# Adafruit_2_8_inch_TFT_w_Capacitive_Touch.net
KiCad netlist of a schematic drawn in EAGLE
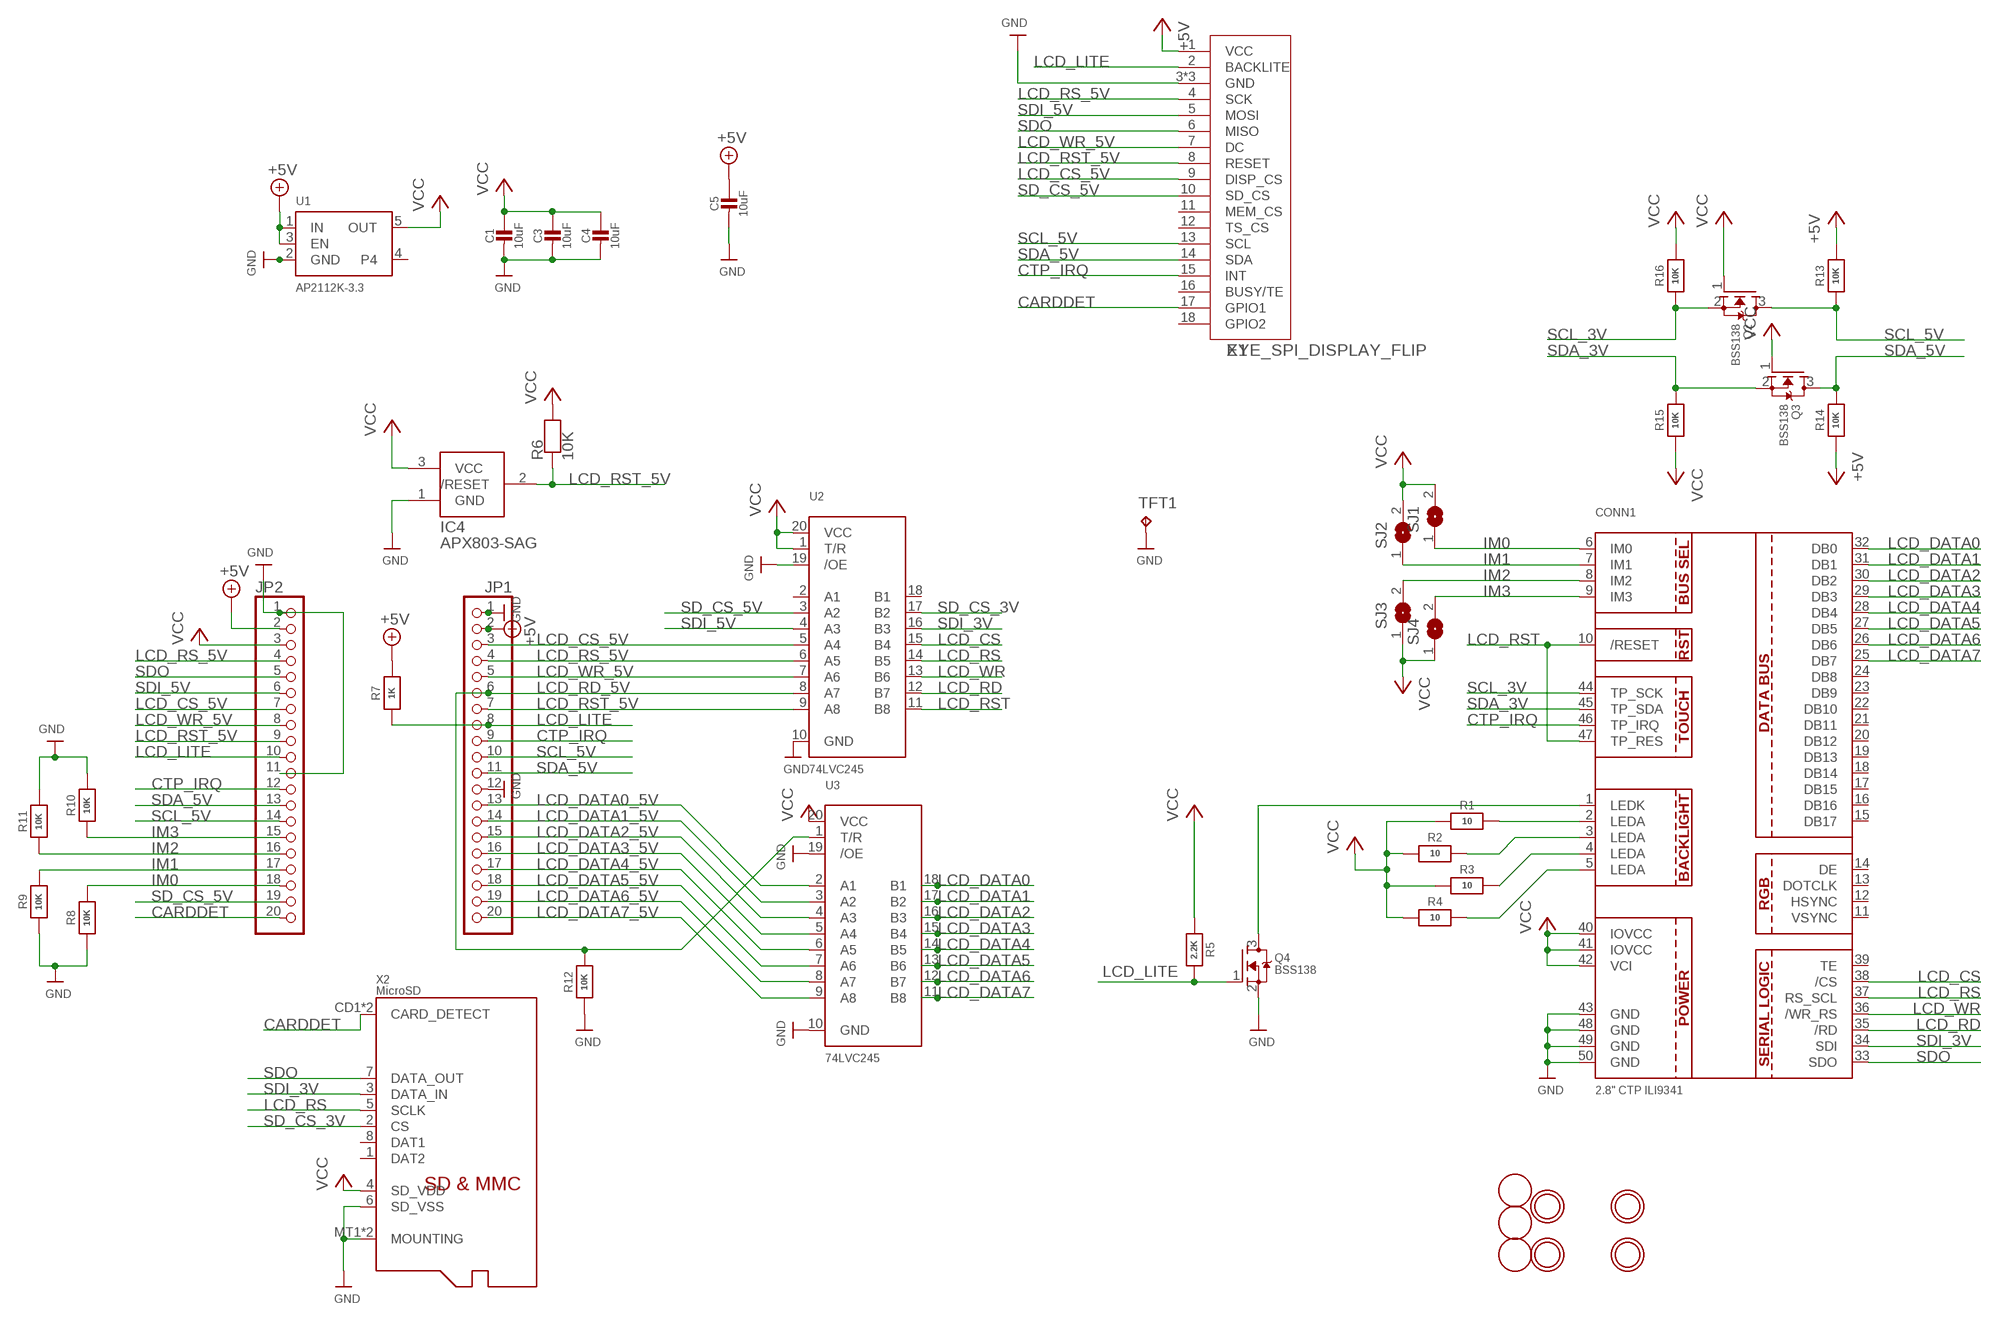
[diagram p0: schematic, sheet 1]

(export (version "E")
  (design (tool "Eeschema 10.0.6"))
  (components
    (comp (ref "C1")
      (value "10uF")
      (footprint "eagle-import:0805-NO")
      (libsource (lib "eagle-import") (part "CAP_CERAMIC0805-NOOUTLINE"))
    )
    (comp (ref "C3")
      (value "10uF")
      (footprint "eagle-import:0805-NO")
      (libsource (lib "eagle-import") (part "CAP_CERAMIC0805-NOOUTLINE"))
    )
    (comp (ref "C4")
      (value "10uF")
      (footprint "eagle-import:0805-NO")
      (libsource (lib "eagle-import") (part "CAP_CERAMIC0805-NOOUTLINE"))
    )
    (comp (ref "C5")
      (value "10uF")
      (footprint "eagle-import:0805-NO")
      (libsource (lib "eagle-import") (part "CAP_CERAMIC0805-NOOUTLINE"))
    )
    (comp (ref "CONN1")
      (value "2.8\" CTP ILI9341")
      (footprint "eagle-import:TFT_2.83IN_240X320_50PIN")
      (libsource (lib "eagle-import") (part "DISP_LCD_CTP28_SAMPLE"))
    )
    (comp (ref "IC4")
      (value "APX803-SAG")
      (footprint "eagle-import:SOT23-WIDE")
      (libsource (lib "eagle-import") (part "APX083-SAG"))
    )
    (comp (ref "JP1")
      (value "HEADER-1X20ROUND")
      (footprint "eagle-import:1X20_ROUND")
      (libsource (lib "eagle-import") (part "HEADER-1X20ROUND"))
    )
    (comp (ref "JP2")
      (value "HEADER-1X20ROUND")
      (footprint "eagle-import:1X20_ROUND")
      (libsource (lib "eagle-import") (part "HEADER-1X20ROUND"))
    )
    (comp (ref "Q2")
      (value "BSS138")
      (footprint "eagle-import:SOT23-WIDE")
      (libsource (lib "eagle-import") (part "MOSFET-NWIDE"))
    )
    (comp (ref "Q3")
      (value "BSS138")
      (footprint "eagle-import:SOT23-WIDE")
      (libsource (lib "eagle-import") (part "MOSFET-NWIDE"))
    )
    (comp (ref "Q4")
      (value "BSS138")
      (footprint "eagle-import:SOT23-WIDE")
      (libsource (lib "eagle-import") (part "MOSFET-NWIDE"))
    )
    (comp (ref "R1")
      (value "10")
      (footprint "eagle-import:0603-NO")
      (libsource (lib "eagle-import") (part "RESISTOR_0603_NOOUT"))
    )
    (comp (ref "R2")
      (value "10")
      (footprint "eagle-import:0603-NO")
      (libsource (lib "eagle-import") (part "RESISTOR_0603_NOOUT"))
    )
    (comp (ref "R3")
      (value "10")
      (footprint "eagle-import:0603-NO")
      (libsource (lib "eagle-import") (part "RESISTOR_0603_NOOUT"))
    )
    (comp (ref "R4")
      (value "10")
      (footprint "eagle-import:0603-NO")
      (libsource (lib "eagle-import") (part "RESISTOR_0603_NOOUT"))
    )
    (comp (ref "R5")
      (value "2.2K")
      (footprint "eagle-import:0603-NO")
      (libsource (lib "eagle-import") (part "RESISTOR_0603_NOOUT"))
    )
    (comp (ref "R6")
      (value "10K")
      (footprint "eagle-import:0603-NO")
      (libsource (lib "eagle-import") (part "RESISTOR_0603_NOOUT"))
    )
    (comp (ref "R7")
      (value "1K")
      (footprint "eagle-import:0603-NO")
      (libsource (lib "eagle-import") (part "RESISTOR_0603_NOOUT"))
    )
    (comp (ref "R8")
      (value "10K")
      (footprint "eagle-import:0603-NO")
      (libsource (lib "eagle-import") (part "RESISTOR_0603_NOOUT"))
    )
    (comp (ref "R9")
      (value "10K")
      (footprint "eagle-import:0603-NO")
      (libsource (lib "eagle-import") (part "RESISTOR_0603_NOOUT"))
    )
    (comp (ref "R10")
      (value "10K")
      (footprint "eagle-import:0603-NO")
      (libsource (lib "eagle-import") (part "RESISTOR_0603_NOOUT"))
    )
    (comp (ref "R11")
      (value "10K")
      (footprint "eagle-import:0603-NO")
      (libsource (lib "eagle-import") (part "RESISTOR_0603_NOOUT"))
    )
    (comp (ref "R12")
      (value "10K")
      (footprint "eagle-import:0603-NO")
      (libsource (lib "eagle-import") (part "RESISTOR_0603_NOOUT"))
    )
    (comp (ref "R13")
      (value "10K")
      (footprint "eagle-import:0603-NO")
      (libsource (lib "eagle-import") (part "RESISTOR_0603_NOOUT"))
    )
    (comp (ref "R14")
      (value "10K")
      (footprint "eagle-import:0603-NO")
      (libsource (lib "eagle-import") (part "RESISTOR_0603_NOOUT"))
    )
    (comp (ref "R15")
      (value "10K")
      (footprint "eagle-import:0603-NO")
      (libsource (lib "eagle-import") (part "RESISTOR_0603_NOOUT"))
    )
    (comp (ref "R16")
      (value "10K")
      (footprint "eagle-import:0603-NO")
      (libsource (lib "eagle-import") (part "RESISTOR_0603_NOOUT"))
    )
    (comp (ref "SJ1")
      (value "SOLDERJUMPER")
      (footprint "eagle-import:SOLDERJUMPER_ARROW_NOPASTE")
      (libsource (lib "eagle-import") (part "SOLDERJUMPER"))
    )
    (comp (ref "SJ2")
      (value "SOLDERJUMPER")
      (footprint "eagle-import:SOLDERJUMPER_ARROW_NOPASTE")
      (libsource (lib "eagle-import") (part "SOLDERJUMPER"))
    )
    (comp (ref "SJ3")
      (value "SOLDERJUMPER")
      (footprint "eagle-import:SOLDERJUMPER_ARROW_NOPASTE")
      (libsource (lib "eagle-import") (part "SOLDERJUMPER"))
    )
    (comp (ref "SJ4")
      (value "SOLDERJUMPER")
      (footprint "eagle-import:SOLDERJUMPER_ARROW_NOPASTE")
      (libsource (lib "eagle-import") (part "SOLDERJUMPER"))
    )
    (comp (ref "TFT1")
      (value "2.8in CTP TFT")
      (footprint "eagle-import:TP06R")
      (libsource (lib "eagle-import") (part "TPTP06R"))
    )
    (comp (ref "U$7")
      (value "MOUNTINGHOLE3.0THIN")
      (footprint "eagle-import:MOUNTINGHOLE_3.0_PLATEDTHIN")
      (libsource (lib "eagle-import") (part "MOUNTINGHOLE3.0THIN"))
    )
    (comp (ref "U$9")
      (value "FIDUCIAL")
      (footprint "eagle-import:FIDUCIAL_1MM")
      (libsource (lib "eagle-import") (part "FIDUCIAL"))
    )
    (comp (ref "U$11")
      (value "FIDUCIAL")
      (footprint "eagle-import:FIDUCIAL_1MM")
      (libsource (lib "eagle-import") (part "FIDUCIAL"))
    )
    (comp (ref "U$15")
      (value "MOUNTINGHOLE3.0THIN")
      (footprint "eagle-import:MOUNTINGHOLE_3.0_PLATEDTHIN")
      (libsource (lib "eagle-import") (part "MOUNTINGHOLE3.0THIN"))
    )
    (comp (ref "U$16")
      (value "MOUNTINGHOLE3.0THIN")
      (footprint "eagle-import:MOUNTINGHOLE_3.0_PLATEDTHIN")
      (libsource (lib "eagle-import") (part "MOUNTINGHOLE3.0THIN"))
    )
    (comp (ref "U$17")
      (value "MOUNTINGHOLE3.0THIN")
      (footprint "eagle-import:MOUNTINGHOLE_3.0_PLATEDTHIN")
      (libsource (lib "eagle-import") (part "MOUNTINGHOLE3.0THIN"))
    )
    (comp (ref "U$23")
      (value "FIDUCIAL")
      (footprint "eagle-import:FIDUCIAL_1MM")
      (libsource (lib "eagle-import") (part "FIDUCIAL"))
    )
    (comp (ref "U1")
      (value "AP2112K-3.3")
      (footprint "eagle-import:SOT23-5")
      (fields (field (name "JLC_ROTATION") "0"))
      (libsource (lib "eagle-import") (part "VREG_SOT23-5"))
    )
    (comp (ref "U2")
      (value "74LVC245")
      (footprint "eagle-import:TSSOP20")
      (libsource (lib "eagle-import") (part "74LCX245_TSSOP20"))
    )
    (comp (ref "U3")
      (value "74LVC245")
      (footprint "eagle-import:TSSOP20")
      (libsource (lib "eagle-import") (part "74LCX245_TSSOP20"))
    )
    (comp (ref "X1")
      (value "EYE_SPI_DISPLAY_FLIP")
      (footprint "eagle-import:EYE_SPI_DISPLAY_BOTCONTACT")
      (libsource (lib "eagle-import") (part "EYE_SPI_DISPLAY_FLIP"))
    )
    (comp (ref "X2")
      (value "MicroSD")
      (footprint "eagle-import:MICROSD")
      (libsource (lib "eagle-import") (part "MICROSD"))
    )
  )
  (nets
    (net (code "1") (name "+5V") (class "Default")
      (node (ref "C5") (pin "1") (pinfunction "1_1") (pintype "passive"))
      (node (ref "JP1") (pin "2") (pinfunction "2_2") (pintype "passive"))
      (node (ref "JP2") (pin "2") (pinfunction "2_2") (pintype "passive"))
      (node (ref "R13") (pin "2") (pinfunction "2_2") (pintype "passive"))
      (node (ref "R14") (pin "1") (pinfunction "1_1") (pintype "passive"))
      (node (ref "R7") (pin "2") (pinfunction "2_2") (pintype "passive"))
      (node (ref "U1") (pin "1") (pinfunction "IN_1") (pintype "power_in"))
      (node (ref "U1") (pin "3") (pinfunction "EN_3") (pintype "input"))
      (node (ref "X1") (pin "1") (pinfunction "VCC_1") (pintype "power_in"))
    )
    (net (code "2") (name "/CARDDET") (class "Default")
      (node (ref "JP2") (pin "20") (pinfunction "20_20") (pintype "passive"))
      (node (ref "X1") (pin "17") (pinfunction "GPIO1_17") (pintype "passive"))
      (node (ref "X2") (pin "CD1") (pinfunction "CARD_DETECT_CD1") (pintype "passive"))
      (node (ref "X2") (pin "CD2") (pinfunction "CARD_DETECT_CD2") (pintype "passive"))
    )
    (net (code "3") (name "/CTP_IRQ") (class "Default")
      (node (ref "CONN1") (pin "46") (pinfunction "TP_IRQ_46") (pintype "bidirectional"))
      (node (ref "JP1") (pin "9") (pinfunction "9_9") (pintype "passive"))
      (node (ref "JP2") (pin "12") (pinfunction "12_12") (pintype "passive"))
      (node (ref "X1") (pin "15") (pinfunction "INT_15") (pintype "output"))
    )
    (net (code "4") (name "/IM0") (class "Default")
      (node (ref "CONN1") (pin "6") (pinfunction "IM0_6") (pintype "bidirectional"))
      (node (ref "JP2") (pin "18") (pinfunction "18_18") (pintype "passive"))
      (node (ref "R8") (pin "2") (pinfunction "2_2") (pintype "passive"))
      (node (ref "SJ1") (pin "1") (pinfunction "1_1") (pintype "passive"))
    )
    (net (code "5") (name "/IM1") (class "Default")
      (node (ref "CONN1") (pin "7") (pinfunction "IM1_7") (pintype "bidirectional"))
      (node (ref "JP2") (pin "17") (pinfunction "17_17") (pintype "passive"))
      (node (ref "R9") (pin "2") (pinfunction "2_2") (pintype "passive"))
      (node (ref "SJ2") (pin "1") (pinfunction "1_1") (pintype "passive"))
    )
    (net (code "6") (name "/IM2") (class "Default")
      (node (ref "CONN1") (pin "8") (pinfunction "IM2_8") (pintype "bidirectional"))
      (node (ref "JP2") (pin "16") (pinfunction "16_16") (pintype "passive"))
      (node (ref "R11") (pin "1") (pinfunction "1_1") (pintype "passive"))
      (node (ref "SJ3") (pin "2") (pinfunction "2_2") (pintype "passive"))
    )
    (net (code "7") (name "/IM3") (class "Default")
      (node (ref "CONN1") (pin "9") (pinfunction "IM3_9") (pintype "bidirectional"))
      (node (ref "JP2") (pin "15") (pinfunction "15_15") (pintype "passive"))
      (node (ref "R10") (pin "1") (pinfunction "1_1") (pintype "passive"))
      (node (ref "SJ4") (pin "2") (pinfunction "2_2") (pintype "passive"))
    )
    (net (code "8") (name "/LCD_CS") (class "Default")
      (node (ref "CONN1") (pin "38") (pinfunction "/CS_38") (pintype "bidirectional"))
      (node (ref "U2") (pin "15") (pinfunction "B4_15") (pintype "bidirectional"))
    )
    (net (code "9") (name "/LCD_CS_5V") (class "Default")
      (node (ref "JP1") (pin "3") (pinfunction "3_3") (pintype "passive"))
      (node (ref "JP2") (pin "7") (pinfunction "7_7") (pintype "passive"))
      (node (ref "U2") (pin "5") (pinfunction "A4_5") (pintype "bidirectional"))
      (node (ref "X1") (pin "9") (pinfunction "DISP_CS_9") (pintype "input"))
    )
    (net (code "10") (name "/LCD_DATA0") (class "Default")
      (node (ref "CONN1") (pin "32") (pinfunction "DB0_32") (pintype "bidirectional"))
      (node (ref "U3") (pin "18") (pinfunction "B1_18") (pintype "bidirectional"))
    )
    (net (code "11") (name "/LCD_DATA0_5V") (class "Default")
      (node (ref "JP1") (pin "13") (pinfunction "13_13") (pintype "passive"))
      (node (ref "U3") (pin "2") (pinfunction "A1_2") (pintype "bidirectional"))
    )
    (net (code "12") (name "/LCD_DATA1") (class "Default")
      (node (ref "CONN1") (pin "31") (pinfunction "DB1_31") (pintype "bidirectional"))
      (node (ref "U3") (pin "17") (pinfunction "B2_17") (pintype "bidirectional"))
    )
    (net (code "13") (name "/LCD_DATA1_5V") (class "Default")
      (node (ref "JP1") (pin "14") (pinfunction "14_14") (pintype "passive"))
      (node (ref "U3") (pin "3") (pinfunction "A2_3") (pintype "bidirectional"))
    )
    (net (code "14") (name "/LCD_DATA2") (class "Default")
      (node (ref "CONN1") (pin "30") (pinfunction "DB2_30") (pintype "bidirectional"))
      (node (ref "U3") (pin "16") (pinfunction "B3_16") (pintype "bidirectional"))
    )
    (net (code "15") (name "/LCD_DATA2_5V") (class "Default")
      (node (ref "JP1") (pin "15") (pinfunction "15_15") (pintype "passive"))
      (node (ref "U3") (pin "4") (pinfunction "A3_4") (pintype "bidirectional"))
    )
    (net (code "16") (name "/LCD_DATA3") (class "Default")
      (node (ref "CONN1") (pin "29") (pinfunction "DB3_29") (pintype "bidirectional"))
      (node (ref "U3") (pin "15") (pinfunction "B4_15") (pintype "bidirectional"))
    )
    (net (code "17") (name "/LCD_DATA3_5V") (class "Default")
      (node (ref "JP1") (pin "16") (pinfunction "16_16") (pintype "passive"))
      (node (ref "U3") (pin "5") (pinfunction "A4_5") (pintype "bidirectional"))
    )
    (net (code "18") (name "/LCD_DATA4") (class "Default")
      (node (ref "CONN1") (pin "28") (pinfunction "DB4_28") (pintype "bidirectional"))
      (node (ref "U3") (pin "14") (pinfunction "B5_14") (pintype "bidirectional"))
    )
    (net (code "19") (name "/LCD_DATA4_5V") (class "Default")
      (node (ref "JP1") (pin "17") (pinfunction "17_17") (pintype "passive"))
      (node (ref "U3") (pin "6") (pinfunction "A5_6") (pintype "bidirectional"))
    )
    (net (code "20") (name "/LCD_DATA5") (class "Default")
      (node (ref "CONN1") (pin "27") (pinfunction "DB5_27") (pintype "bidirectional"))
      (node (ref "U3") (pin "13") (pinfunction "B6_13") (pintype "bidirectional"))
    )
    (net (code "21") (name "/LCD_DATA5_5V") (class "Default")
      (node (ref "JP1") (pin "18") (pinfunction "18_18") (pintype "passive"))
      (node (ref "U3") (pin "7") (pinfunction "A6_7") (pintype "bidirectional"))
    )
    (net (code "22") (name "/LCD_DATA6") (class "Default")
      (node (ref "CONN1") (pin "26") (pinfunction "DB6_26") (pintype "bidirectional"))
      (node (ref "U3") (pin "12") (pinfunction "B7_12") (pintype "bidirectional"))
    )
    (net (code "23") (name "/LCD_DATA6_5V") (class "Default")
      (node (ref "JP1") (pin "19") (pinfunction "19_19") (pintype "passive"))
      (node (ref "U3") (pin "8") (pinfunction "A7_8") (pintype "bidirectional"))
    )
    (net (code "24") (name "/LCD_DATA7") (class "Default")
      (node (ref "CONN1") (pin "25") (pinfunction "DB7_25") (pintype "bidirectional"))
      (node (ref "U3") (pin "11") (pinfunction "B8_11") (pintype "bidirectional"))
    )
    (net (code "25") (name "/LCD_DATA7_5V") (class "Default")
      (node (ref "JP1") (pin "20") (pinfunction "20_20") (pintype "passive"))
      (node (ref "U3") (pin "9") (pinfunction "A8_9") (pintype "bidirectional"))
    )
    (net (code "26") (name "/LCD_LITE") (class "Default")
      (node (ref "JP1") (pin "8") (pinfunction "8_8") (pintype "passive"))
      (node (ref "JP2") (pin "10") (pinfunction "10_10") (pintype "passive"))
      (node (ref "Q4") (pin "1") (pinfunction "G_1") (pintype "bidirectional"))
      (node (ref "R5") (pin "2") (pinfunction "2_2") (pintype "passive"))
      (node (ref "R7") (pin "1") (pinfunction "1_1") (pintype "passive"))
      (node (ref "X1") (pin "2") (pinfunction "BACKLITE_2") (pintype "input"))
    )
    (net (code "27") (name "/LCD_RD") (class "Default")
      (node (ref "CONN1") (pin "35") (pinfunction "/RD_35") (pintype "bidirectional"))
      (node (ref "U2") (pin "12") (pinfunction "B7_12") (pintype "bidirectional"))
    )
    (net (code "28") (name "/LCD_RD_5V") (class "Default")
      (node (ref "JP1") (pin "6") (pinfunction "6_6") (pintype "passive"))
      (node (ref "R12") (pin "2") (pinfunction "2_2") (pintype "passive"))
      (node (ref "U2") (pin "8") (pinfunction "A7_8") (pintype "bidirectional"))
      (node (ref "U3") (pin "1") (pinfunction "T/R_1") (pintype "bidirectional"))
    )
    (net (code "29") (name "/LCD_RS") (class "Default")
      (node (ref "CONN1") (pin "37") (pinfunction "RS_SCL_37") (pintype "bidirectional"))
      (node (ref "U2") (pin "14") (pinfunction "B5_14") (pintype "bidirectional"))
      (node (ref "X2") (pin "5") (pinfunction "SCLK_5") (pintype "input"))
    )
    (net (code "30") (name "/LCD_RST") (class "Default")
      (node (ref "CONN1") (pin "10") (pinfunction "/RESET_10") (pintype "bidirectional"))
      (node (ref "CONN1") (pin "47") (pinfunction "TP_RES_47") (pintype "bidirectional"))
      (node (ref "U2") (pin "11") (pinfunction "B8_11") (pintype "bidirectional"))
    )
    (net (code "31") (name "/LCD_RST_5V") (class "Default")
      (node (ref "IC4") (pin "2") (pinfunction "/RESET_2") (pintype "output"))
      (node (ref "JP1") (pin "7") (pinfunction "7_7") (pintype "passive"))
      (node (ref "JP2") (pin "9") (pinfunction "9_9") (pintype "passive"))
      (node (ref "R6") (pin "1") (pinfunction "1_1") (pintype "passive"))
      (node (ref "U2") (pin "9") (pinfunction "A8_9") (pintype "bidirectional"))
      (node (ref "X1") (pin "8") (pinfunction "RESET_8") (pintype "input"))
    )
    (net (code "32") (name "/LCD_RS_5V") (class "Default")
      (node (ref "JP1") (pin "4") (pinfunction "4_4") (pintype "passive"))
      (node (ref "JP2") (pin "4") (pinfunction "4_4") (pintype "passive"))
      (node (ref "U2") (pin "6") (pinfunction "A5_6") (pintype "bidirectional"))
      (node (ref "X1") (pin "4") (pinfunction "SCK_4") (pintype "input"))
    )
    (net (code "33") (name "/LCD_WR") (class "Default")
      (node (ref "CONN1") (pin "36") (pinfunction "/WR_RS_36") (pintype "bidirectional"))
      (node (ref "U2") (pin "13") (pinfunction "B6_13") (pintype "bidirectional"))
    )
    (net (code "34") (name "/LCD_WR_5V") (class "Default")
      (node (ref "JP1") (pin "5") (pinfunction "5_5") (pintype "passive"))
      (node (ref "JP2") (pin "8") (pinfunction "8_8") (pintype "passive"))
      (node (ref "U2") (pin "7") (pinfunction "A6_7") (pintype "bidirectional"))
      (node (ref "X1") (pin "7") (pinfunction "DC_7") (pintype "input"))
    )
    (net (code "35") (name "/SCL_3V") (class "Default")
      (node (ref "CONN1") (pin "44") (pinfunction "TP_SCK_44") (pintype "bidirectional"))
      (node (ref "Q2") (pin "2") (pinfunction "S_2") (pintype "bidirectional"))
      (node (ref "R16") (pin "1") (pinfunction "1_1") (pintype "passive"))
    )
    (net (code "36") (name "/SCL_5V") (class "Default")
      (node (ref "JP1") (pin "10") (pinfunction "10_10") (pintype "passive"))
      (node (ref "JP2") (pin "14") (pinfunction "14_14") (pintype "passive"))
      (node (ref "Q2") (pin "3") (pinfunction "D_3") (pintype "bidirectional"))
      (node (ref "R13") (pin "1") (pinfunction "1_1") (pintype "passive"))
      (node (ref "X1") (pin "13") (pinfunction "SCL_13") (pintype "input"))
    )
    (net (code "37") (name "/SDA_3V") (class "Default")
      (node (ref "CONN1") (pin "45") (pinfunction "TP_SDA_45") (pintype "bidirectional"))
      (node (ref "Q3") (pin "2") (pinfunction "S_2") (pintype "bidirectional"))
      (node (ref "R15") (pin "2") (pinfunction "2_2") (pintype "passive"))
    )
    (net (code "38") (name "/SDA_5V") (class "Default")
      (node (ref "JP1") (pin "11") (pinfunction "11_11") (pintype "passive"))
      (node (ref "JP2") (pin "13") (pinfunction "13_13") (pintype "passive"))
      (node (ref "Q3") (pin "3") (pinfunction "D_3") (pintype "bidirectional"))
      (node (ref "R14") (pin "2") (pinfunction "2_2") (pintype "passive"))
      (node (ref "X1") (pin "14") (pinfunction "SDA_14") (pintype "bidirectional"))
    )
    (net (code "39") (name "/SDI_3V") (class "Default")
      (node (ref "CONN1") (pin "34") (pinfunction "SDI_34") (pintype "bidirectional"))
      (node (ref "U2") (pin "16") (pinfunction "B3_16") (pintype "bidirectional"))
      (node (ref "X2") (pin "3") (pinfunction "DATA_IN_3") (pintype "input"))
    )
    (net (code "40") (name "/SDI_5V") (class "Default")
      (node (ref "JP2") (pin "6") (pinfunction "6_6") (pintype "passive"))
      (node (ref "U2") (pin "4") (pinfunction "A3_4") (pintype "bidirectional"))
      (node (ref "X1") (pin "5") (pinfunction "MOSI_5") (pintype "input"))
    )
    (net (code "41") (name "/SDO") (class "Default")
      (node (ref "CONN1") (pin "33") (pinfunction "SDO_33") (pintype "bidirectional"))
      (node (ref "JP2") (pin "5") (pinfunction "5_5") (pintype "passive"))
      (node (ref "X1") (pin "6") (pinfunction "MISO_6") (pintype "output"))
      (node (ref "X2") (pin "7") (pinfunction "DATA_OUT_7") (pintype "output"))
    )
    (net (code "42") (name "/SD_CS_3V") (class "Default")
      (node (ref "U2") (pin "17") (pinfunction "B2_17") (pintype "bidirectional"))
      (node (ref "X2") (pin "2") (pinfunction "CS_2") (pintype "input"))
    )
    (net (code "43") (name "/SD_CS_5V") (class "Default")
      (node (ref "JP2") (pin "19") (pinfunction "19_19") (pintype "passive"))
      (node (ref "U2") (pin "3") (pinfunction "A2_3") (pintype "bidirectional"))
      (node (ref "X1") (pin "10") (pinfunction "SD_CS_10") (pintype "input"))
    )
    (net (code "44") (name "GND") (class "Default")
      (node (ref "C1") (pin "2") (pinfunction "2_2") (pintype "passive"))
      (node (ref "C3") (pin "2") (pinfunction "2_2") (pintype "passive"))
      (node (ref "C4") (pin "2") (pinfunction "2_2") (pintype "passive"))
      (node (ref "C5") (pin "2") (pinfunction "2_2") (pintype "passive"))
      (node (ref "CONN1") (pin "43") (pinfunction "GND_43") (pintype "bidirectional"))
      (node (ref "CONN1") (pin "48") (pinfunction "GND_48") (pintype "bidirectional"))
      (node (ref "CONN1") (pin "49") (pinfunction "GND_49") (pintype "bidirectional"))
      (node (ref "CONN1") (pin "50") (pinfunction "GND_50") (pintype "bidirectional"))
      (node (ref "IC4") (pin "1") (pinfunction "GND_1") (pintype "power_in"))
      (node (ref "JP1") (pin "1") (pinfunction "1_1") (pintype "passive"))
      (node (ref "JP1") (pin "12") (pinfunction "12_12") (pintype "passive"))
      (node (ref "JP2") (pin "1") (pinfunction "1_1") (pintype "passive"))
      (node (ref "JP2") (pin "11") (pinfunction "11_11") (pintype "passive"))
      (node (ref "Q4") (pin "2") (pinfunction "S_2") (pintype "bidirectional"))
      (node (ref "R10") (pin "2") (pinfunction "2_2") (pintype "passive"))
      (node (ref "R11") (pin "2") (pinfunction "2_2") (pintype "passive"))
      (node (ref "R12") (pin "1") (pinfunction "1_1") (pintype "passive"))
      (node (ref "R8") (pin "1") (pinfunction "1_1") (pintype "passive"))
      (node (ref "R9") (pin "1") (pinfunction "1_1") (pintype "passive"))
      (node (ref "TFT1") (pin "TP") (pinfunction "TP_TP") (pintype "input"))
      (node (ref "U1") (pin "2") (pinfunction "GND_2") (pintype "power_in"))
      (node (ref "U2") (pin "10") (pinfunction "GND_10") (pintype "bidirectional"))
      (node (ref "U2") (pin "19") (pinfunction "/OE_19") (pintype "bidirectional"))
      (node (ref "U3") (pin "10") (pinfunction "GND_10") (pintype "bidirectional"))
      (node (ref "U3") (pin "19") (pinfunction "/OE_19") (pintype "bidirectional"))
      (node (ref "X1") (pin "3") (pinfunction "GND_3") (pintype "power_in"))
      (node (ref "X1") (pin "SUPPORT1") (pinfunction "GND_SUPPORT1") (pintype "power_in"))
      (node (ref "X1") (pin "SUPPORT2") (pinfunction "GND_SUPPORT2") (pintype "power_in"))
      (node (ref "X2") (pin "6") (pinfunction "SD_VSS_6") (pintype "power_in"))
      (node (ref "X2") (pin "MT1") (pinfunction "MOUNTING_MT1") (pintype "passive"))
      (node (ref "X2") (pin "MT2") (pinfunction "MOUNTING_MT2") (pintype "passive"))
    )
    (net (code "45") (name "Net-(CONN1-LEDA-Pad2)") (class "Default")
      (node (ref "CONN1") (pin "2") (pinfunction "LEDA_2") (pintype "bidirectional"))
      (node (ref "R1") (pin "2") (pinfunction "2_2") (pintype "passive"))
    )
    (net (code "46") (name "Net-(CONN1-LEDA-Pad3)") (class "Default")
      (node (ref "CONN1") (pin "3") (pinfunction "LEDA_3") (pintype "bidirectional"))
      (node (ref "R2") (pin "2") (pinfunction "2_2") (pintype "passive"))
    )
    (net (code "47") (name "Net-(CONN1-LEDA-Pad4)") (class "Default")
      (node (ref "CONN1") (pin "4") (pinfunction "LEDA_4") (pintype "bidirectional"))
      (node (ref "R3") (pin "2") (pinfunction "2_2") (pintype "passive"))
    )
    (net (code "48") (name "Net-(CONN1-LEDA-Pad5)") (class "Default")
      (node (ref "CONN1") (pin "5") (pinfunction "LEDA_5") (pintype "bidirectional"))
      (node (ref "R4") (pin "2") (pinfunction "2_2") (pintype "passive"))
    )
    (net (code "49") (name "Net-(CONN1-LEDK)") (class "Default")
      (node (ref "CONN1") (pin "1") (pinfunction "LEDK_1") (pintype "bidirectional"))
      (node (ref "Q4") (pin "3") (pinfunction "D_3") (pintype "bidirectional"))
    )
    (net (code "50") (name "VCC") (class "Default")
      (node (ref "C1") (pin "1") (pinfunction "1_1") (pintype "passive"))
      (node (ref "C3") (pin "1") (pinfunction "1_1") (pintype "passive"))
      (node (ref "C4") (pin "1") (pinfunction "1_1") (pintype "passive"))
      (node (ref "CONN1") (pin "40") (pinfunction "IOVCC_40") (pintype "bidirectional"))
      (node (ref "CONN1") (pin "41") (pinfunction "IOVCC_41") (pintype "bidirectional"))
      (node (ref "CONN1") (pin "42") (pinfunction "VCI_42") (pintype "bidirectional"))
      (node (ref "IC4") (pin "3") (pinfunction "VCC_3") (pintype "power_in"))
      (node (ref "JP2") (pin "3") (pinfunction "3_3") (pintype "passive"))
      (node (ref "Q2") (pin "1") (pinfunction "G_1") (pintype "bidirectional"))
      (node (ref "Q3") (pin "1") (pinfunction "G_1") (pintype "bidirectional"))
      (node (ref "R1") (pin "1") (pinfunction "1_1") (pintype "passive"))
      (node (ref "R15") (pin "1") (pinfunction "1_1") (pintype "passive"))
      (node (ref "R16") (pin "2") (pinfunction "2_2") (pintype "passive"))
      (node (ref "R2") (pin "1") (pinfunction "1_1") (pintype "passive"))
      (node (ref "R3") (pin "1") (pinfunction "1_1") (pintype "passive"))
      (node (ref "R4") (pin "1") (pinfunction "1_1") (pintype "passive"))
      (node (ref "R5") (pin "1") (pinfunction "1_1") (pintype "passive"))
      (node (ref "R6") (pin "2") (pinfunction "2_2") (pintype "passive"))
      (node (ref "SJ1") (pin "2") (pinfunction "2_2") (pintype "passive"))
      (node (ref "SJ2") (pin "2") (pinfunction "2_2") (pintype "passive"))
      (node (ref "SJ3") (pin "1") (pinfunction "1_1") (pintype "passive"))
      (node (ref "SJ4") (pin "1") (pinfunction "1_1") (pintype "passive"))
      (node (ref "U1") (pin "5") (pinfunction "OUT_5") (pintype "power_in"))
      (node (ref "U2") (pin "1") (pinfunction "T/R_1") (pintype "bidirectional"))
      (node (ref "U2") (pin "20") (pinfunction "VCC_20") (pintype "bidirectional"))
      (node (ref "U3") (pin "20") (pinfunction "VCC_20") (pintype "bidirectional"))
      (node (ref "X2") (pin "4") (pinfunction "SD_VDD_4") (pintype "power_in"))
    )
    (net (code "51") (name "unconnected-(CONN1-DB8-Pad24)") (class "Default")
      (node (ref "CONN1") (pin "24") (pinfunction "DB8_24") (pintype "bidirectional"))
    )
    (net (code "52") (name "unconnected-(CONN1-DB9-Pad23)") (class "Default")
      (node (ref "CONN1") (pin "23") (pinfunction "DB9_23") (pintype "bidirectional"))
    )
    (net (code "53") (name "unconnected-(CONN1-DB10-Pad22)") (class "Default")
      (node (ref "CONN1") (pin "22") (pinfunction "DB10_22") (pintype "bidirectional"))
    )
    (net (code "54") (name "unconnected-(CONN1-DB11-Pad21)") (class "Default")
      (node (ref "CONN1") (pin "21") (pinfunction "DB11_21") (pintype "bidirectional"))
    )
    (net (code "55") (name "unconnected-(CONN1-DB12-Pad20)") (class "Default")
      (node (ref "CONN1") (pin "20") (pinfunction "DB12_20") (pintype "bidirectional"))
    )
    (net (code "56") (name "unconnected-(CONN1-DB13-Pad19)") (class "Default")
      (node (ref "CONN1") (pin "19") (pinfunction "DB13_19") (pintype "bidirectional"))
    )
    (net (code "57") (name "unconnected-(CONN1-DB14-Pad18)") (class "Default")
      (node (ref "CONN1") (pin "18") (pinfunction "DB14_18") (pintype "bidirectional"))
    )
    (net (code "58") (name "unconnected-(CONN1-DB15-Pad17)") (class "Default")
      (node (ref "CONN1") (pin "17") (pinfunction "DB15_17") (pintype "bidirectional"))
    )
    (net (code "59") (name "unconnected-(CONN1-DB16-Pad16)") (class "Default")
      (node (ref "CONN1") (pin "16") (pinfunction "DB16_16") (pintype "bidirectional"))
    )
    (net (code "60") (name "unconnected-(CONN1-DB17-Pad15)") (class "Default")
      (node (ref "CONN1") (pin "15") (pinfunction "DB17_15") (pintype "bidirectional"))
    )
    (net (code "61") (name "unconnected-(CONN1-DE-Pad14)") (class "Default")
      (node (ref "CONN1") (pin "14") (pinfunction "DE_14") (pintype "bidirectional"))
    )
    (net (code "62") (name "unconnected-(CONN1-DOTCLK-Pad13)") (class "Default")
      (node (ref "CONN1") (pin "13") (pinfunction "DOTCLK_13") (pintype "bidirectional"))
    )
    (net (code "63") (name "unconnected-(CONN1-HSYNC-Pad12)") (class "Default")
      (node (ref "CONN1") (pin "12") (pinfunction "HSYNC_12") (pintype "bidirectional"))
    )
    (net (code "64") (name "unconnected-(CONN1-TE-Pad39)") (class "Default")
      (node (ref "CONN1") (pin "39") (pinfunction "TE_39") (pintype "bidirectional"))
    )
    (net (code "65") (name "unconnected-(CONN1-VSYNC-Pad11)") (class "Default")
      (node (ref "CONN1") (pin "11") (pinfunction "VSYNC_11") (pintype "bidirectional"))
    )
    (net (code "66") (name "unconnected-(U1-P4-Pad4)") (class "Default")
      (node (ref "U1") (pin "4") (pinfunction "P4_4") (pintype "bidirectional"))
    )
    (net (code "67") (name "unconnected-(U2-A1-Pad2)") (class "Default")
      (node (ref "U2") (pin "2") (pinfunction "A1_2") (pintype "bidirectional"))
    )
    (net (code "68") (name "unconnected-(U2-B1-Pad18)") (class "Default")
      (node (ref "U2") (pin "18") (pinfunction "B1_18") (pintype "bidirectional"))
    )
    (net (code "69") (name "unconnected-(X1-BUSY{slash}TE-Pad16)") (class "Default")
      (node (ref "X1") (pin "16") (pinfunction "BUSY/TE_16") (pintype "output"))
    )
    (net (code "70") (name "unconnected-(X1-GPIO2-Pad18)") (class "Default")
      (node (ref "X1") (pin "18") (pinfunction "GPIO2_18") (pintype "passive"))
    )
    (net (code "71") (name "unconnected-(X1-MEM_CS-Pad11)") (class "Default")
      (node (ref "X1") (pin "11") (pinfunction "MEM_CS_11") (pintype "input"))
    )
    (net (code "72") (name "unconnected-(X1-TS_CS-Pad12)") (class "Default")
      (node (ref "X1") (pin "12") (pinfunction "TS_CS_12") (pintype "input"))
    )
    (net (code "73") (name "unconnected-(X2-DAT1-Pad8)") (class "Default")
      (node (ref "X2") (pin "8") (pinfunction "DAT1_8") (pintype "bidirectional"))
    )
    (net (code "74") (name "unconnected-(X2-DAT2-Pad1)") (class "Default")
      (node (ref "X2") (pin "1") (pinfunction "DAT2_1") (pintype "bidirectional"))
    )
  )
)
